# CPLD_Breakout.net
KiCad netlist of a schematic drawn in Altium Designer
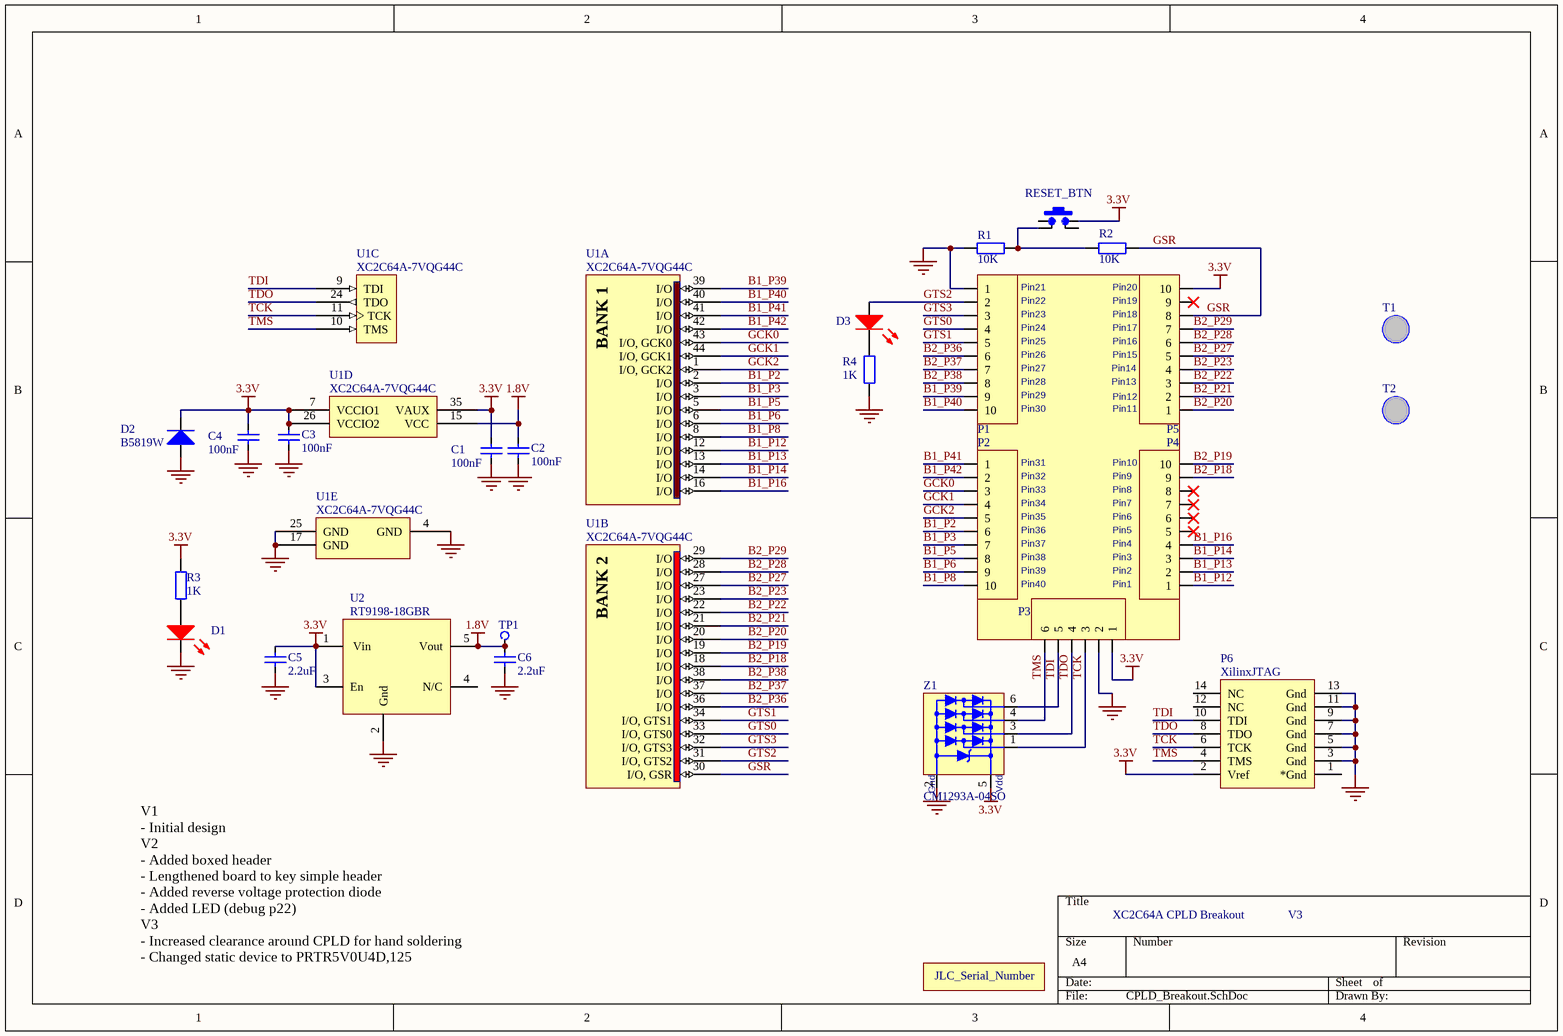
[diagram p0: CPLD_Breakout.SchDoc]

(export (version "E")
  (design (tool "Eeschema 10.0.6"))
  (components
    (comp (ref "C1")
      (value "100nF")
      (footprint "CCNP1608-0603")
      (description "Capacitor non-polar SMT 0603")
      (fields
        (field (name "MANUFACTURER") "Generic Components")
        (field (name "PUBLISHER") "Altium Hobart Technology Centre")
      )
      (libsource (lib "MyLibrary") (part "Cap_CCNP_0603"))
    )
    (comp (ref "C2")
      (value "100nF")
      (footprint "CCNP1608-0603")
      (description "Capacitor non-polar SMT 0603")
      (fields
        (field (name "MANUFACTURER") "Generic Components")
        (field (name "PUBLISHER") "Altium Hobart Technology Centre")
      )
      (libsource (lib "MyLibrary") (part "Cap_CCNP_0603"))
    )
    (comp (ref "C3")
      (value "100nF")
      (footprint "CCNP1608-0603")
      (description "Capacitor non-polar SMT 0603")
      (fields
        (field (name "MANUFACTURER") "Generic Components")
        (field (name "PUBLISHER") "Altium Hobart Technology Centre")
      )
      (libsource (lib "MyLibrary") (part "Cap_CCNP_0603"))
    )
    (comp (ref "C4")
      (value "100nF")
      (footprint "CCNP1608-0603")
      (description "Capacitor non-polar SMT 0603")
      (fields
        (field (name "MANUFACTURER") "Generic Components")
        (field (name "PUBLISHER") "Altium Hobart Technology Centre")
      )
      (libsource (lib "MyLibrary") (part "Cap_CCNP_0603"))
    )
    (comp (ref "C5")
      (value "2.2uF")
      (footprint "CCNP1608-0603")
      (description "Capacitor")
      (fields
        (field (name "MANUFACTURER") "Generic Components")
        (field (name "PUBLISHER") "Altium Hobart Technology Centre")
      )
      (libsource (lib "MyLibrary") (part "Cap"))
    )
    (comp (ref "C6")
      (value "2.2uF")
      (footprint "CCNP1608-0603")
      (description "Capacitor")
      (fields
        (field (name "MANUFACTURER") "Generic Components")
        (field (name "PUBLISHER") "Altium Hobart Technology Centre")
      )
      (libsource (lib "MyLibrary") (part "Cap"))
    )
    (comp (ref "D1")
      (value "LED Red")
      (footprint "LED1608-0603-RED")
      (description "LED 0603 Red")
      (fields (field (name "MANUFACTURER") "Generic Components") (field (name "PUBLISHER") "Altium Limited"))
      (libsource (lib "MySchLib") (part "LED-0603-Red"))
    )
    (comp (ref "D2")
      (value "B5819W")
      (footprint "SOD-123")
      (description "Schottky diode1A 40V Vrm SOD-123")
      (fields
        (field (name "MANUFACTURER") "Generic Components")
        (field (name "PUBLISHER") "Altium Hobart Technology Centre")
      )
      (libsource (lib "MyLibrary") (part "B5819W"))
    )
    (comp (ref "D3")
      (value "LED Red")
      (footprint "LED1608-0603-RED")
      (description "LED 0603 Red")
      (fields (field (name "MANUFACTURER") "Generic Components") (field (name "PUBLISHER") "Altium Limited"))
      (libsource (lib "MySchLib") (part "LED-0603-Red"))
    )
    (comp (ref "JLC_Serial_Number")
      (value "JLC_Serial_Number")
      (footprint "JLC_Serial_Number")
      (libsource (lib "MyLibrary") (part "JLC_Serial_Number"))
    )
    (comp (ref "P1")
      (value "Header, 10-Pin")
      (footprint "HDR1X10S")
      (fields (field (name "PUBLISHER") "Altium Limited"))
      (libsource (lib "MyLibrary") (part "Header 1x10"))
    )
    (comp (ref "P2")
      (value "Header, 10-Pin")
      (footprint "HDR1X10S")
      (fields (field (name "PUBLISHER") "Altium Limited"))
      (libsource (lib "MyLibrary") (part "Header 1x10"))
    )
    (comp (ref "P3")
      (value "Header, 6-Pin")
      (footprint "HDR1X6S")
      (fields (field (name "PUBLISHER") "Altium Limited"))
      (libsource (lib "MyLibrary") (part "Header 1x6"))
    )
    (comp (ref "P4")
      (value "Header, 10-Pin")
      (footprint "HDR1X10S")
      (fields (field (name "PUBLISHER") "Altium Limited"))
      (libsource (lib "") (part "Header 1x10_1"))
    )
    (comp (ref "P5")
      (value "Header, 10-Pin")
      (footprint "HDR1X10S")
      (fields (field (name "PUBLISHER") "Altium Limited"))
      (libsource (lib "") (part "Header 1x10_1"))
    )
    (comp (ref "P6")
      (value "XilinxJTAG")
      (footprint "HEADER_2x7_2mm")
      (libsource (lib "MySchLib") (part "XilinxJTAG"))
    )
    (comp (ref "R1")
      (value "10K")
      (footprint "CR1608-0603")
      (description "Resistor SMT 0603")
      (fields
        (field (name "MANUFACTURER") "Generic Components")
        (field (name "PUBLISHER") "Altium Hobart Technology Centre")
      )
      (libsource (lib "MyLibrary") (part "Res_CR0603"))
    )
    (comp (ref "R2")
      (value "10K")
      (footprint "CR1608-0603")
      (description "Resistor SMT 0603")
      (fields
        (field (name "MANUFACTURER") "Generic Components")
        (field (name "PUBLISHER") "Altium Hobart Technology Centre")
      )
      (libsource (lib "MyLibrary") (part "Res_CR0603"))
    )
    (comp (ref "R3")
      (value "1K")
      (footprint "CR1608-0603")
      (description "Resistor SMT 0603")
      (fields
        (field (name "MANUFACTURER") "Generic Components")
        (field (name "PUBLISHER") "Altium Hobart Technology Centre")
      )
      (libsource (lib "") (part "Res_CR0603_1"))
    )
    (comp (ref "R4")
      (value "1K")
      (footprint "CR1608-0603")
      (description "Resistor SMT 0603")
      (fields
        (field (name "MANUFACTURER") "Generic Components")
        (field (name "PUBLISHER") "Altium Hobart Technology Centre")
      )
      (libsource (lib "") (part "Res_CR0603_1"))
    )
    (comp (ref "RESET_BTN")
      (value "SMD-SW-4_5.1x5.1x2.0_M")
      (footprint "SMD-SW-4_5.1x5.1x2.0_M")
      (description "Tactile Switch SPST 5.10mm X 5.10mm\r\n(1.5mm=C318884)\r\n(2.0mm=C318888)\r\n(3.5mm=C318886)")
      (libsource (lib "MySchLib") (part "SW_PB-TS"))
    )
    (comp (ref "T1")
      (value "Tooling Hole")
      (footprint "JLCPCB_Tooling_Hole")
      (libsource (lib "MySchLib") (part "JLC_Tooling_Hole"))
    )
    (comp (ref "T2")
      (value "Tooling Hole")
      (footprint "JLCPCB_Tooling_Hole")
      (libsource (lib "MySchLib") (part "JLC_Tooling_Hole"))
    )
    (comp (ref "TP1")
      (value "1.8V")
      (footprint "PCBPIN - 0.7mm")
      (description "Test Point")
      (libsource (lib "MyLibrary") (part "TP"))
    )
    (comp (ref "U1")
      (value "XC2C64A-7VQG44C")
      (footprint "VQG44_M")
      (description "CoolRunner-II 1.8V, 64 Macrocell CPLD, 33 User I/Os, 44-Pin VQFP, Commercial Grade, Pb-Free")
      (libsource (lib "MySchLib") (part "XC2C64-7VQ44C"))
    )
    (comp (ref "U2")
      (value "RT9198-18GBR")
      (footprint "SOT23-5")
      (description "1.8V 300mA LDO with enable, uses low ESR cap (ceramic)")
      (libsource (lib "MySchLib") (part "RT9198-18GBR"))
    )
    (comp (ref "Z1")
      (value "CM1293A-04SO")
      (footprint "SOT457_N")
      (description "Ultra low capacitance quadruple rail-to-rail ESD protection")
      (libsource (lib "MySchLib") (part "CM1293A-04SO"))
    )
  )
  (nets
    (net (code "1") (name "/B1_P2") (class "Default")
      (node (ref "P2") (pin "6") (pinfunction "6_6") (pintype "passive"))
      (node (ref "U1") (pin "2") (pinfunction "I/O_2") (pintype "bidirectional"))
    )
    (net (code "2") (name "/B1_P3") (class "Default")
      (node (ref "P2") (pin "7") (pinfunction "7_7") (pintype "passive"))
      (node (ref "U1") (pin "3") (pinfunction "I/O_3") (pintype "bidirectional"))
    )
    (net (code "3") (name "/B1_P5") (class "Default")
      (node (ref "P2") (pin "8") (pinfunction "8_8") (pintype "passive"))
      (node (ref "U1") (pin "5") (pinfunction "I/O_5") (pintype "bidirectional"))
    )
    (net (code "4") (name "/B1_P6") (class "Default")
      (node (ref "P2") (pin "9") (pinfunction "9_9") (pintype "passive"))
      (node (ref "U1") (pin "6") (pinfunction "I/O_6") (pintype "bidirectional"))
    )
    (net (code "5") (name "/B1_P8") (class "Default")
      (node (ref "P2") (pin "10") (pinfunction "10_10") (pintype "passive"))
      (node (ref "U1") (pin "8") (pinfunction "I/O_8") (pintype "bidirectional"))
    )
    (net (code "6") (name "/B1_P12") (class "Default")
      (node (ref "P4") (pin "1") (pinfunction "1_1") (pintype "passive"))
      (node (ref "U1") (pin "12") (pinfunction "I/O_12") (pintype "bidirectional"))
    )
    (net (code "7") (name "/B1_P13") (class "Default")
      (node (ref "P4") (pin "2") (pinfunction "2_2") (pintype "passive"))
      (node (ref "U1") (pin "13") (pinfunction "I/O_13") (pintype "bidirectional"))
    )
    (net (code "8") (name "/B1_P14") (class "Default")
      (node (ref "P4") (pin "3") (pinfunction "3_3") (pintype "passive"))
      (node (ref "U1") (pin "14") (pinfunction "I/O_14") (pintype "bidirectional"))
    )
    (net (code "9") (name "/B1_P16") (class "Default")
      (node (ref "P4") (pin "4") (pinfunction "4_4") (pintype "passive"))
      (node (ref "U1") (pin "16") (pinfunction "I/O_16") (pintype "bidirectional"))
    )
    (net (code "10") (name "/B1_P39") (class "Default")
      (node (ref "P1") (pin "9") (pinfunction "9_9") (pintype "passive"))
      (node (ref "U1") (pin "39") (pinfunction "I/O_39") (pintype "bidirectional"))
    )
    (net (code "11") (name "/B1_P40") (class "Default")
      (node (ref "P1") (pin "10") (pinfunction "10_10") (pintype "passive"))
      (node (ref "U1") (pin "40") (pinfunction "I/O_40") (pintype "bidirectional"))
    )
    (net (code "12") (name "/B1_P41") (class "Default")
      (node (ref "P2") (pin "1") (pinfunction "1_1") (pintype "passive"))
      (node (ref "U1") (pin "41") (pinfunction "I/O_41") (pintype "bidirectional"))
    )
    (net (code "13") (name "/B1_P42") (class "Default")
      (node (ref "P2") (pin "2") (pinfunction "2_2") (pintype "passive"))
      (node (ref "U1") (pin "42") (pinfunction "I/O_42") (pintype "bidirectional"))
    )
    (net (code "14") (name "/B2_P18") (class "Default")
      (node (ref "P4") (pin "9") (pinfunction "9_9") (pintype "passive"))
      (node (ref "U1") (pin "18") (pinfunction "I/O_18") (pintype "bidirectional"))
    )
    (net (code "15") (name "/B2_P19") (class "Default")
      (node (ref "P4") (pin "10") (pinfunction "10_10") (pintype "passive"))
      (node (ref "U1") (pin "19") (pinfunction "I/O_19") (pintype "bidirectional"))
    )
    (net (code "16") (name "/B2_P20") (class "Default")
      (node (ref "P5") (pin "1") (pinfunction "1_1") (pintype "passive"))
      (node (ref "U1") (pin "20") (pinfunction "I/O_20") (pintype "bidirectional"))
    )
    (net (code "17") (name "/B2_P21") (class "Default")
      (node (ref "P5") (pin "2") (pinfunction "2_2") (pintype "passive"))
      (node (ref "U1") (pin "21") (pinfunction "I/O_21") (pintype "bidirectional"))
    )
    (net (code "18") (name "/B2_P22") (class "Default")
      (node (ref "P5") (pin "3") (pinfunction "3_3") (pintype "passive"))
      (node (ref "U1") (pin "22") (pinfunction "I/O_22") (pintype "bidirectional"))
    )
    (net (code "19") (name "/B2_P23") (class "Default")
      (node (ref "P5") (pin "4") (pinfunction "4_4") (pintype "passive"))
      (node (ref "U1") (pin "23") (pinfunction "I/O_23") (pintype "bidirectional"))
    )
    (net (code "20") (name "/B2_P27") (class "Default")
      (node (ref "P5") (pin "5") (pinfunction "5_5") (pintype "passive"))
      (node (ref "U1") (pin "27") (pinfunction "I/O_27") (pintype "bidirectional"))
    )
    (net (code "21") (name "/B2_P28") (class "Default")
      (node (ref "P5") (pin "6") (pinfunction "6_6") (pintype "passive"))
      (node (ref "U1") (pin "28") (pinfunction "I/O_28") (pintype "bidirectional"))
    )
    (net (code "22") (name "/B2_P29") (class "Default")
      (node (ref "P5") (pin "7") (pinfunction "7_7") (pintype "passive"))
      (node (ref "U1") (pin "29") (pinfunction "I/O_29") (pintype "bidirectional"))
    )
    (net (code "23") (name "/B2_P36") (class "Default")
      (node (ref "P1") (pin "6") (pinfunction "6_6") (pintype "passive"))
      (node (ref "U1") (pin "36") (pinfunction "I/O_36") (pintype "bidirectional"))
    )
    (net (code "24") (name "/B2_P37") (class "Default")
      (node (ref "P1") (pin "7") (pinfunction "7_7") (pintype "passive"))
      (node (ref "U1") (pin "37") (pinfunction "I/O_37") (pintype "bidirectional"))
    )
    (net (code "25") (name "/B2_P38") (class "Default")
      (node (ref "P1") (pin "8") (pinfunction "8_8") (pintype "passive"))
      (node (ref "U1") (pin "38") (pinfunction "I/O_38") (pintype "bidirectional"))
    )
    (net (code "26") (name "/GCK0") (class "Default")
      (node (ref "P2") (pin "3") (pinfunction "3_3") (pintype "passive"))
      (node (ref "U1") (pin "43") (pinfunction "I/O,_GCK0_43") (pintype "bidirectional"))
    )
    (net (code "27") (name "/GCK1") (class "Default")
      (node (ref "P2") (pin "4") (pinfunction "4_4") (pintype "passive"))
      (node (ref "U1") (pin "44") (pinfunction "I/O,_GCK1_44") (pintype "bidirectional"))
    )
    (net (code "28") (name "/GCK2") (class "Default")
      (node (ref "P2") (pin "5") (pinfunction "5_5") (pintype "passive"))
      (node (ref "U1") (pin "1") (pinfunction "I/O,_GCK2_1") (pintype "bidirectional"))
    )
    (net (code "29") (name "/GSR") (class "Default")
      (node (ref "P5") (pin "8") (pinfunction "8_8") (pintype "passive"))
      (node (ref "R2") (pin "1") (pinfunction "1_1") (pintype "passive"))
      (node (ref "U1") (pin "30") (pinfunction "I/O,_GSR_30") (pintype "bidirectional"))
    )
    (net (code "30") (name "/GTS0") (class "Default")
      (node (ref "P1") (pin "4") (pinfunction "4_4") (pintype "passive"))
      (node (ref "U1") (pin "33") (pinfunction "I/O,_GTS0_33") (pintype "bidirectional"))
    )
    (net (code "31") (name "/GTS1") (class "Default")
      (node (ref "P1") (pin "5") (pinfunction "5_5") (pintype "passive"))
      (node (ref "U1") (pin "34") (pinfunction "I/O,_GTS1_34") (pintype "bidirectional"))
    )
    (net (code "32") (name "/GTS2") (class "Default")
      (node (ref "D3") (pin "A") (pinfunction "A_A") (pintype "passive"))
      (node (ref "P1") (pin "2") (pinfunction "2_2") (pintype "passive"))
      (node (ref "U1") (pin "31") (pinfunction "I/O,_GTS2_31") (pintype "bidirectional"))
    )
    (net (code "33") (name "/GTS3") (class "Default")
      (node (ref "P1") (pin "3") (pinfunction "3_3") (pintype "passive"))
      (node (ref "U1") (pin "32") (pinfunction "I/O,_GTS3_32") (pintype "bidirectional"))
    )
    (net (code "34") (name "/TCK") (class "Default")
      (node (ref "P3") (pin "3") (pinfunction "3_3") (pintype "passive"))
      (node (ref "P6") (pin "6") (pinfunction "TCK_6") (pintype "passive"))
      (node (ref "U1") (pin "11") (pinfunction "TCK_11") (pintype "input"))
      (node (ref "Z1") (pin "1") (pintype "passive"))
    )
    (net (code "35") (name "/TDI") (class "Default")
      (node (ref "P3") (pin "5") (pinfunction "5_5") (pintype "passive"))
      (node (ref "P6") (pin "10") (pinfunction "TDI_10") (pintype "passive"))
      (node (ref "U1") (pin "9") (pinfunction "TDI_9") (pintype "input"))
      (node (ref "Z1") (pin "6") (pintype "passive"))
    )
    (net (code "36") (name "/TDO") (class "Default")
      (node (ref "P3") (pin "4") (pinfunction "4_4") (pintype "passive"))
      (node (ref "P6") (pin "8") (pinfunction "TDO_8") (pintype "passive"))
      (node (ref "U1") (pin "24") (pinfunction "TDO_24") (pintype "output"))
      (node (ref "Z1") (pin "3") (pintype "passive"))
    )
    (net (code "37") (name "/TMS") (class "Default")
      (node (ref "P3") (pin "6") (pinfunction "6_6") (pintype "passive"))
      (node (ref "P6") (pin "4") (pinfunction "TMS_4") (pintype "passive"))
      (node (ref "U1") (pin "10") (pinfunction "TMS_10") (pintype "input"))
      (node (ref "Z1") (pin "4") (pintype "passive"))
    )
    (net (code "38") (name "1.8V") (class "Default")
      (node (ref "C2") (pin "2") (pinfunction "2_2") (pintype "passive"))
      (node (ref "C6") (pin "2") (pinfunction "2_2") (pintype "passive"))
      (node (ref "TP1") (pin "1") (pinfunction "TP_1") (pintype "passive"))
      (node (ref "U1") (pin "15") (pinfunction "VCC_15") (pintype "power_in"))
      (node (ref "U2") (pin "5") (pinfunction "Vout_5") (pintype "passive"))
    )
    (net (code "39") (name "3.3V") (class "Default")
      (node (ref "C1") (pin "2") (pinfunction "2_2") (pintype "passive"))
      (node (ref "C3") (pin "2") (pinfunction "2_2") (pintype "passive"))
      (node (ref "C4") (pin "2") (pinfunction "2_2") (pintype "passive"))
      (node (ref "C5") (pin "2") (pinfunction "2_2") (pintype "passive"))
      (node (ref "D2") (pin "K") (pinfunction "K_K") (pintype "passive"))
      (node (ref "P3") (pin "1") (pinfunction "1_1") (pintype "passive"))
      (node (ref "P5") (pin "10") (pinfunction "10_10") (pintype "passive"))
      (node (ref "P6") (pin "2") (pinfunction "Vref_2") (pintype "passive"))
      (node (ref "R3") (pin "2") (pinfunction "2_2") (pintype "passive"))
      (node (ref "RESET_BTN") (pin "1b") (pinfunction "1b_1b") (pintype "passive"))
      (node (ref "U1") (pin "26") (pinfunction "VCCIO2_26") (pintype "power_in"))
      (node (ref "U1") (pin "35") (pinfunction "VAUX_35") (pintype "power_in"))
      (node (ref "U1") (pin "7") (pinfunction "VCCIO1_7") (pintype "power_in"))
      (node (ref "U2") (pin "1") (pinfunction "_Vin_1") (pintype "passive"))
      (node (ref "U2") (pin "3") (pinfunction "En_3") (pintype "passive"))
      (node (ref "Z1") (pin "5") (pinfunction "Vp_5") (pintype "passive"))
    )
    (net (code "40") (name "GND") (class "Default")
      (node (ref "C1") (pin "1") (pinfunction "1_1") (pintype "passive"))
      (node (ref "C2") (pin "1") (pinfunction "1_1") (pintype "passive"))
      (node (ref "C3") (pin "1") (pinfunction "1_1") (pintype "passive"))
      (node (ref "C4") (pin "1") (pinfunction "1_1") (pintype "passive"))
      (node (ref "C5") (pin "1") (pinfunction "1_1") (pintype "passive"))
      (node (ref "C6") (pin "1") (pinfunction "1_1") (pintype "passive"))
      (node (ref "D1") (pin "K") (pinfunction "K_K") (pintype "passive"))
      (node (ref "D2") (pin "A") (pinfunction "A_A") (pintype "passive"))
      (node (ref "P1") (pin "1") (pinfunction "1_1") (pintype "passive"))
      (node (ref "P3") (pin "2") (pinfunction "2_2") (pintype "passive"))
      (node (ref "P6") (pin "11") (pinfunction "Gnd_11") (pintype "passive"))
      (node (ref "P6") (pin "13") (pinfunction "Gnd_13") (pintype "passive"))
      (node (ref "P6") (pin "3") (pinfunction "Gnd_3") (pintype "passive"))
      (node (ref "P6") (pin "5") (pinfunction "Gnd_5") (pintype "passive"))
      (node (ref "P6") (pin "7") (pinfunction "Gnd_7") (pintype "passive"))
      (node (ref "P6") (pin "9") (pinfunction "Gnd_9") (pintype "passive"))
      (node (ref "R1") (pin "2") (pinfunction "2_2") (pintype "passive"))
      (node (ref "R4") (pin "1") (pinfunction "1_1") (pintype "passive"))
      (node (ref "U1") (pin "17") (pinfunction "GND_17") (pintype "power_in"))
      (node (ref "U1") (pin "25") (pinfunction "GND_25") (pintype "power_in"))
      (node (ref "U1") (pin "4") (pinfunction "GND_4") (pintype "power_in"))
      (node (ref "U2") (pin "2") (pinfunction "Gnd_2") (pintype "passive"))
      (node (ref "Z1") (pin "2") (pinfunction "Vn_2") (pintype "passive"))
    )
    (net (code "41") (name "Net-(D1-PadA)") (class "Default")
      (node (ref "D1") (pin "A") (pinfunction "A_A") (pintype "passive"))
      (node (ref "R3") (pin "1") (pinfunction "1_1") (pintype "passive"))
    )
    (net (code "42") (name "Net-(D3-PadK)") (class "Default")
      (node (ref "D3") (pin "K") (pinfunction "K_K") (pintype "passive"))
      (node (ref "R4") (pin "2") (pinfunction "2_2") (pintype "passive"))
    )
    (net (code "43") (name "Net-(R1-Pad1)") (class "Default")
      (node (ref "R1") (pin "1") (pinfunction "1_1") (pintype "passive"))
      (node (ref "R2") (pin "2") (pinfunction "2_2") (pintype "passive"))
      (node (ref "RESET_BTN") (pin "2") (pinfunction "2_2") (pintype "passive"))
    )
    (net (code "44") (name "unconnected-(P4-Pad5)") (class "Default")
      (node (ref "P4") (pin "5") (pinfunction "5_5") (pintype "passive+no_connect"))
    )
    (net (code "45") (name "unconnected-(P4-Pad6)") (class "Default")
      (node (ref "P4") (pin "6") (pinfunction "6_6") (pintype "passive+no_connect"))
    )
    (net (code "46") (name "unconnected-(P4-Pad7)") (class "Default")
      (node (ref "P4") (pin "7") (pinfunction "7_7") (pintype "passive+no_connect"))
    )
    (net (code "47") (name "unconnected-(P4-Pad8)") (class "Default")
      (node (ref "P4") (pin "8") (pinfunction "8_8") (pintype "passive+no_connect"))
    )
    (net (code "48") (name "unconnected-(P5-Pad9)") (class "Default")
      (node (ref "P5") (pin "9") (pinfunction "9_9") (pintype "passive+no_connect"))
    )
    (net (code "49") (name "unconnected-(P6-*Gnd-Pad1)") (class "Default")
      (node (ref "P6") (pin "1") (pinfunction "*Gnd_1") (pintype "passive"))
    )
    (net (code "50") (name "unconnected-(P6-NC-Pad12)") (class "Default")
      (node (ref "P6") (pin "12") (pinfunction "NC_12") (pintype "passive"))
    )
    (net (code "51") (name "unconnected-(P6-NC-Pad14)") (class "Default")
      (node (ref "P6") (pin "14") (pinfunction "NC_14") (pintype "passive"))
    )
    (net (code "52") (name "unconnected-(RESET_BTN-Pad1)") (class "Default")
      (node (ref "RESET_BTN") (pin "1") (pinfunction "1_1") (pintype "passive"))
    )
    (net (code "53") (name "unconnected-(RESET_BTN-Pad2b)") (class "Default")
      (node (ref "RESET_BTN") (pin "2b") (pinfunction "2b_2b") (pintype "passive"))
    )
    (net (code "54") (name "unconnected-(U2-N{slash}C-Pad4)") (class "Default")
      (node (ref "U2") (pin "4") (pinfunction "N/C_4") (pintype "passive"))
    )
  )
)
